# Awesome-Shield-1_0.net
KiCad netlist of a schematic drawn in EAGLE
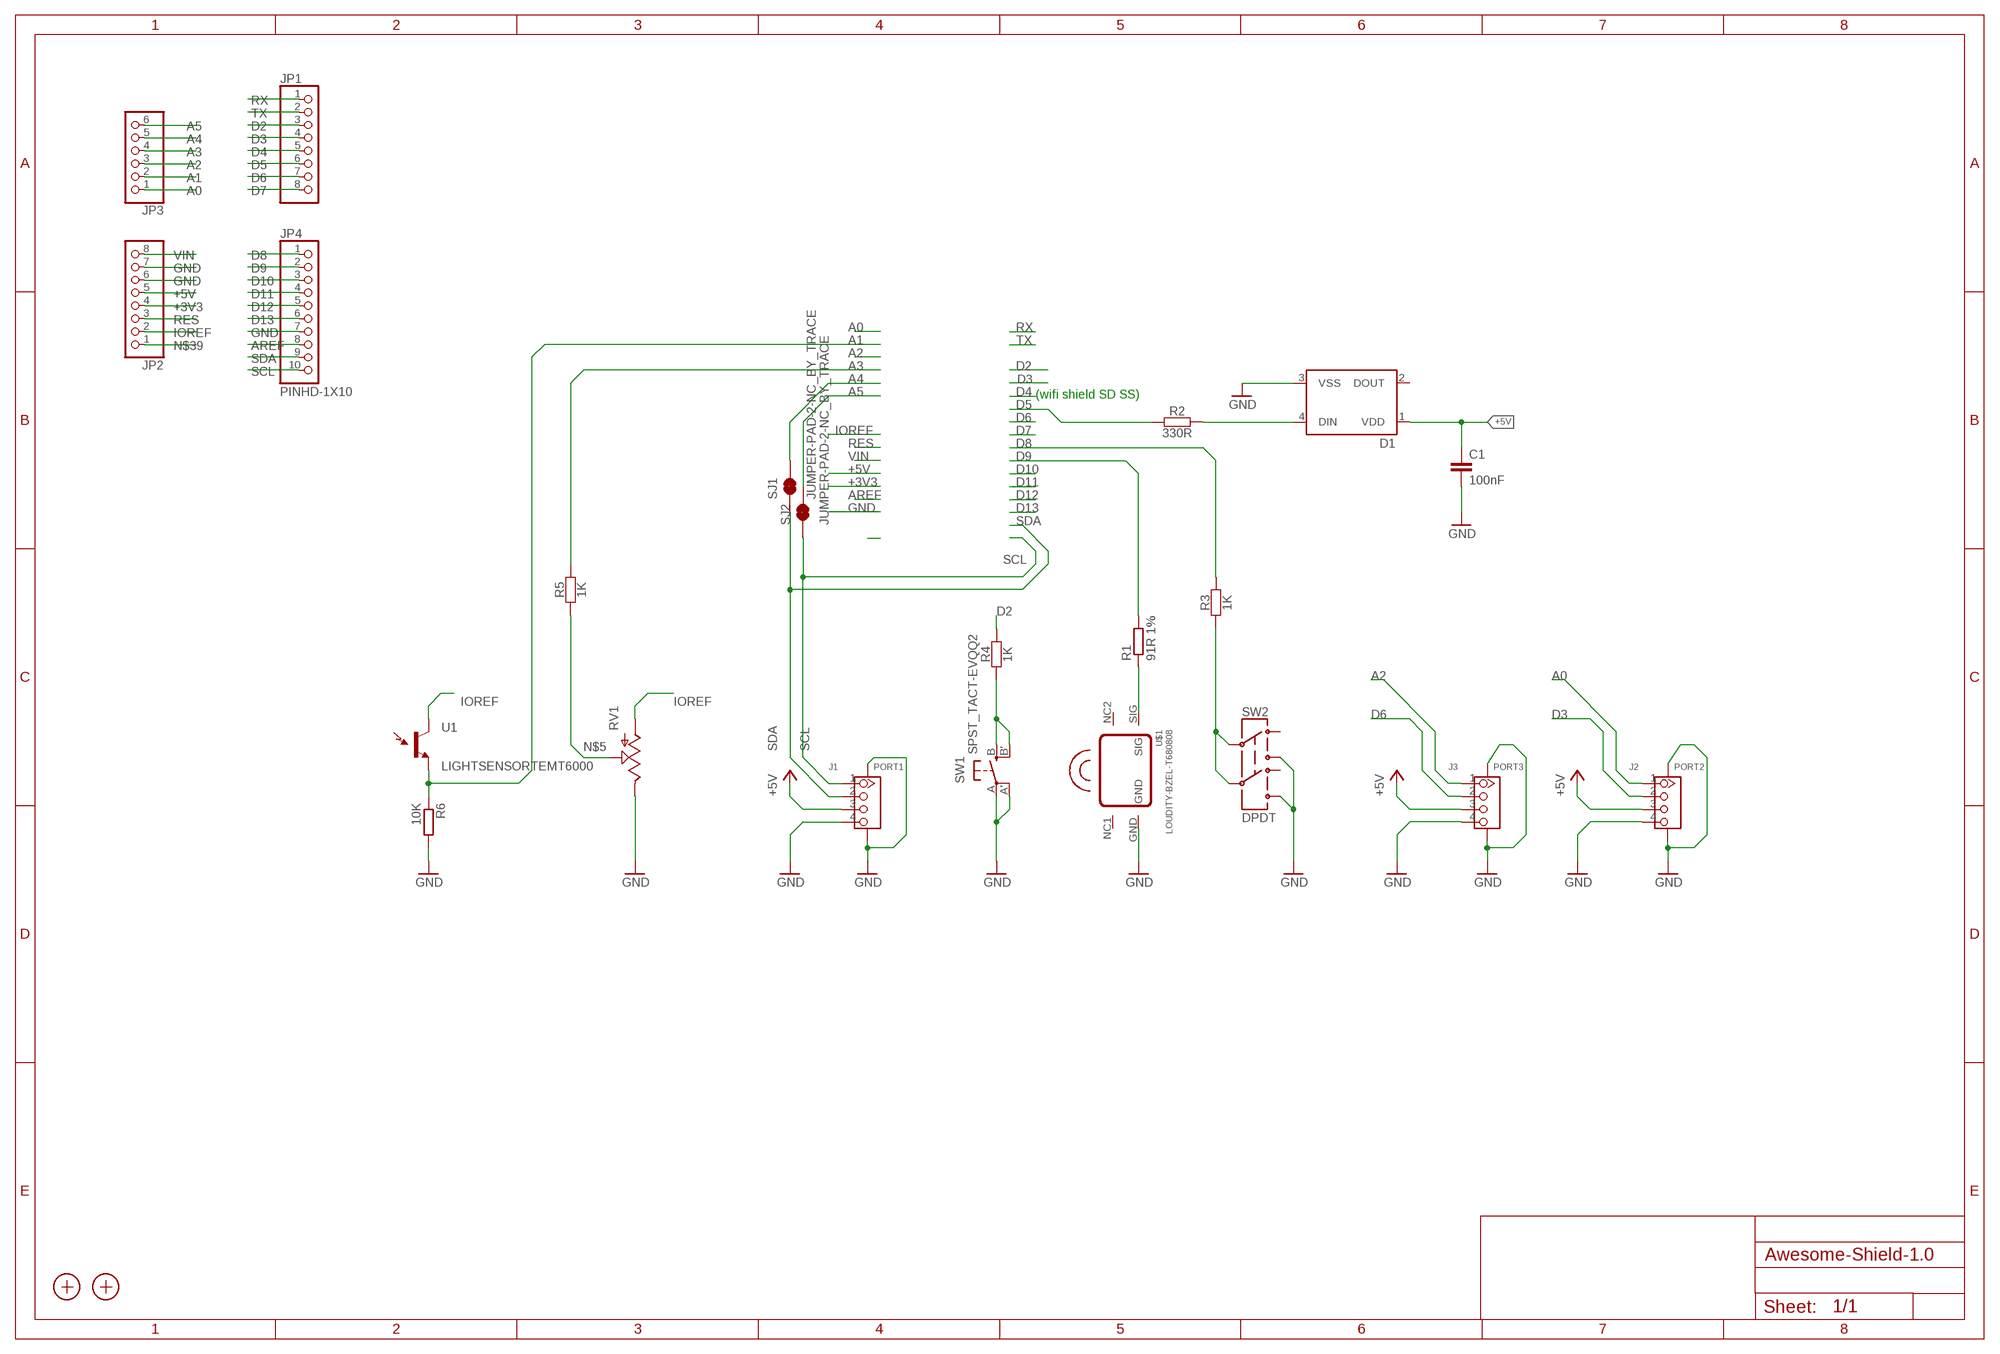
[diagram p0: schematic, sheet 1]

(export (version "E")
  (design (tool "Eeschema 10.0.6"))
  (components
    (comp (ref "C1")
      (value "100nF")
      (footprint "eagle-import:C0603")
      (libsource (lib "eagle-import") (part "C-EUC0603"))
    )
    (comp (ref "D1")
      (value "WS2812B")
      (footprint "eagle-import:WS2812B")
      (libsource (lib "eagle-import") (part "WS2812B"))
    )
    (comp (ref "J1")
      (value "PORT1")
      (footprint "eagle-import:HW4-SMD-2.0")
      (libsource (lib "eagle-import") (part "GROVE-CONNECTOR-SMD(4+2P-2.0)"))
    )
    (comp (ref "J2")
      (value "PORT2")
      (footprint "eagle-import:HW4-SMD-2.0")
      (libsource (lib "eagle-import") (part "GROVE-CONNECTOR-SMD(4+2P-2.0)"))
    )
    (comp (ref "J3")
      (value "PORT3")
      (footprint "eagle-import:HW4-SMD-2.0")
      (libsource (lib "eagle-import") (part "GROVE-CONNECTOR-SMD(4+2P-2.0)"))
    )
    (comp (ref "JP1")
      (value "PINHD-1X8CLEANBIG")
      (footprint "eagle-import:1X08-CLEANBIG")
      (libsource (lib "eagle-import") (part "PINHD-1X8CLEANBIG"))
    )
    (comp (ref "JP2")
      (value "PINHD-1X8CLEANBIG")
      (footprint "eagle-import:1X08-CLEANBIG")
      (libsource (lib "eagle-import") (part "PINHD-1X8CLEANBIG"))
    )
    (comp (ref "JP3")
      (value "PINHD-1X6CLEAN")
      (footprint "eagle-import:1X06-CLEAN")
      (libsource (lib "eagle-import") (part "PINHD-1X6CLEAN"))
    )
    (comp (ref "JP4")
      (value "PINHD-1X10")
      (footprint "eagle-import:1X10-BIG")
      (libsource (lib "eagle-import") (part "PINHD-1X10"))
    )
    (comp (ref "R1")
      (value "91R 1%")
      (footprint "eagle-import:R1206")
      (libsource (lib "eagle-import") (part "R-EU_R1206"))
    )
    (comp (ref "R2")
      (value "330R")
      (footprint "eagle-import:C1206")
      (libsource (lib "eagle-import") (part "RESISTOR-1206"))
    )
    (comp (ref "R3")
      (value "1K")
      (footprint "eagle-import:C0603")
      (libsource (lib "eagle-import") (part "RESISTOR-0603"))
    )
    (comp (ref "R4")
      (value "1K")
      (footprint "eagle-import:C0603")
      (libsource (lib "eagle-import") (part "RESISTOR-0603"))
    )
    (comp (ref "R5")
      (value "1K")
      (footprint "eagle-import:C0603")
      (libsource (lib "eagle-import") (part "RESISTOR-0603"))
    )
    (comp (ref "R6")
      (value "10K")
      (footprint "eagle-import:R1206")
      (libsource (lib "eagle-import") (part "R-EU_R1206"))
    )
    (comp (ref "RV1")
      (value "POT")
      (footprint "eagle-import:ALPS_POT")
      (libsource (lib "eagle-import") (part "POT"))
    )
    (comp (ref "SJ1")
      (value "JUMPER-PAD-2-NC_BY_TRACE")
      (footprint "eagle-import:PAD-JUMPER-2-NC_BY_TRACE_YES_SILK")
      (libsource (lib "eagle-import") (part "JUMPER-PAD-2-NC_BY_TRACE"))
    )
    (comp (ref "SJ2")
      (value "JUMPER-PAD-2-NC_BY_TRACE")
      (footprint "eagle-import:PAD-JUMPER-2-NC_BY_TRACE_YES_SILK")
      (libsource (lib "eagle-import") (part "JUMPER-PAD-2-NC_BY_TRACE"))
    )
    (comp (ref "SW1")
      (value "SPST_TACT-EVQQ2")
      (footprint "eagle-import:EVQ-Q2")
      (libsource (lib "eagle-import") (part "SPST_TACT-EVQQ2"))
    )
    (comp (ref "SW2")
      (value "DPDT")
      (footprint "eagle-import:AYZ0202")
      (libsource (lib "eagle-import") (part "SWITCH-DPDTAYZ0202"))
    )
    (comp (ref "U$1")
      (value "LOUDITY-BZEL-T680808")
      (footprint "eagle-import:SMT-68")
      (libsource (lib "eagle-import") (part "LOUDITY-BZEL-T680808"))
    )
    (comp (ref "U1")
      (value "LIGHTSENSORTEMT6000")
      (footprint "eagle-import:TEMT6000-SEN")
      (libsource (lib "eagle-import") (part "LIGHTSENSORTEMT6000"))
    )
    (comp (ref "X1")
      (value "PASSER-07")
      (footprint "eagle-import:PASSER_07MM")
      (libsource (lib "eagle-import") (part "PASSER-07"))
    )
    (comp (ref "X2")
      (value "PASSER-07")
      (footprint "eagle-import:PASSER_07MM")
      (libsource (lib "eagle-import") (part "PASSER-07"))
    )
  )
  (nets
    (net (code "1") (name "+5V") (class "Default")
      (node (ref "C1") (pin "1") (pinfunction "1_1") (pintype "passive"))
      (node (ref "D1") (pin "1") (pinfunction "VDD_1") (pintype "power_in"))
      (node (ref "J1") (pin "3") (pinfunction "3_3") (pintype "bidirectional"))
      (node (ref "J2") (pin "3") (pinfunction "3_3") (pintype "bidirectional"))
      (node (ref "J3") (pin "3") (pinfunction "3_3") (pintype "bidirectional"))
      (node (ref "JP2") (pin "5") (pinfunction "5_5") (pintype "passive"))
    )
    (net (code "2") (name "/+3V3") (class "Default")
      (node (ref "JP2") (pin "4") (pinfunction "4_4") (pintype "passive"))
    )
    (net (code "3") (name "/A0") (class "Default")
      (node (ref "J2") (pin "1") (pinfunction "1_1") (pintype "bidirectional"))
      (node (ref "JP3") (pin "1") (pinfunction "1_1") (pintype "passive"))
    )
    (net (code "4") (name "/A1") (class "Default")
      (node (ref "JP3") (pin "2") (pinfunction "2_2") (pintype "passive"))
      (node (ref "R6") (pin "1") (pinfunction "1_1") (pintype "passive"))
      (node (ref "U1") (pin "EMITTER") (pinfunction "E1_EMITTER") (pintype "passive"))
    )
    (net (code "5") (name "/A2") (class "Default")
      (node (ref "J3") (pin "1") (pinfunction "1_1") (pintype "bidirectional"))
      (node (ref "JP3") (pin "3") (pinfunction "3_3") (pintype "passive"))
    )
    (net (code "6") (name "/A3") (class "Default")
      (node (ref "JP3") (pin "4") (pinfunction "4_4") (pintype "passive"))
      (node (ref "R5") (pin "2") (pinfunction "2_2") (pintype "passive"))
    )
    (net (code "7") (name "/A4") (class "Default")
      (node (ref "JP3") (pin "5") (pinfunction "5_5") (pintype "passive"))
      (node (ref "SJ1") (pin "2") (pinfunction "2_2") (pintype "passive"))
    )
    (net (code "8") (name "/A5") (class "Default")
      (node (ref "JP3") (pin "6") (pinfunction "6_6") (pintype "passive"))
      (node (ref "SJ2") (pin "2") (pinfunction "2_2") (pintype "passive"))
    )
    (net (code "9") (name "/AREF") (class "Default")
      (node (ref "JP4") (pin "8") (pinfunction "8_8") (pintype "passive"))
    )
    (net (code "10") (name "/D2") (class "Default")
      (node (ref "JP1") (pin "3") (pinfunction "3_3") (pintype "passive"))
      (node (ref "R4") (pin "2") (pinfunction "2_2") (pintype "passive"))
    )
    (net (code "11") (name "/D3") (class "Default")
      (node (ref "J2") (pin "2") (pinfunction "2_2") (pintype "bidirectional"))
      (node (ref "JP1") (pin "4") (pinfunction "4_4") (pintype "passive"))
    )
    (net (code "12") (name "/D4") (class "Default")
      (node (ref "JP1") (pin "5") (pinfunction "5_5") (pintype "passive"))
    )
    (net (code "13") (name "/D5") (class "Default")
      (node (ref "JP1") (pin "6") (pinfunction "6_6") (pintype "passive"))
      (node (ref "R2") (pin "1") (pinfunction "1_1") (pintype "passive"))
    )
    (net (code "14") (name "/D6") (class "Default")
      (node (ref "J3") (pin "2") (pinfunction "2_2") (pintype "bidirectional"))
      (node (ref "JP1") (pin "7") (pinfunction "7_7") (pintype "passive"))
    )
    (net (code "15") (name "/D7") (class "Default")
      (node (ref "JP1") (pin "8") (pinfunction "8_8") (pintype "passive"))
    )
    (net (code "16") (name "/D8") (class "Default")
      (node (ref "JP4") (pin "1") (pinfunction "1_1") (pintype "passive"))
      (node (ref "R3") (pin "2") (pinfunction "2_2") (pintype "passive"))
    )
    (net (code "17") (name "/D9") (class "Default")
      (node (ref "JP4") (pin "2") (pinfunction "2_2") (pintype "passive"))
      (node (ref "R1") (pin "2") (pinfunction "2_2") (pintype "passive"))
    )
    (net (code "18") (name "/D10") (class "Default")
      (node (ref "JP4") (pin "3") (pinfunction "3_3") (pintype "passive"))
    )
    (net (code "19") (name "/D11") (class "Default")
      (node (ref "JP4") (pin "4") (pinfunction "4_4") (pintype "passive"))
    )
    (net (code "20") (name "/D12") (class "Default")
      (node (ref "JP4") (pin "5") (pinfunction "5_5") (pintype "passive"))
    )
    (net (code "21") (name "/D13") (class "Default")
      (node (ref "JP4") (pin "6") (pinfunction "6_6") (pintype "passive"))
    )
    (net (code "22") (name "/IOREF") (class "Default")
      (node (ref "JP2") (pin "2") (pinfunction "2_2") (pintype "passive"))
      (node (ref "RV1") (pin "P$3") (pinfunction "A_P$3") (pintype "passive"))
      (node (ref "U1") (pin "COLLECTOR") (pinfunction "C1_COLLECTOR") (pintype "passive"))
    )
    (net (code "23") (name "/N$5") (class "Default")
      (node (ref "R5") (pin "1") (pinfunction "1_1") (pintype "passive"))
      (node (ref "RV1") (pin "P$2") (pinfunction "S_P$2") (pintype "passive"))
    )
    (net (code "24") (name "/N$39") (class "Default")
      (node (ref "JP2") (pin "1") (pinfunction "1_1") (pintype "passive"))
    )
    (net (code "25") (name "/RES") (class "Default")
      (node (ref "JP2") (pin "3") (pinfunction "3_3") (pintype "passive"))
    )
    (net (code "26") (name "/RX") (class "Default")
      (node (ref "JP1") (pin "1") (pinfunction "1_1") (pintype "passive"))
    )
    (net (code "27") (name "/SCL") (class "Default")
      (node (ref "J1") (pin "1") (pinfunction "1_1") (pintype "bidirectional"))
      (node (ref "JP4") (pin "10") (pinfunction "10_10") (pintype "passive"))
      (node (ref "SJ2") (pin "1") (pinfunction "1_1") (pintype "passive"))
    )
    (net (code "28") (name "/SDA") (class "Default")
      (node (ref "J1") (pin "2") (pinfunction "2_2") (pintype "bidirectional"))
      (node (ref "JP4") (pin "9") (pinfunction "9_9") (pintype "passive"))
      (node (ref "SJ1") (pin "1") (pinfunction "1_1") (pintype "passive"))
    )
    (net (code "29") (name "/TX") (class "Default")
      (node (ref "JP1") (pin "2") (pinfunction "2_2") (pintype "passive"))
    )
    (net (code "30") (name "/VIN") (class "Default")
      (node (ref "JP2") (pin "8") (pinfunction "8_8") (pintype "passive"))
    )
    (net (code "31") (name "GND") (class "Default")
      (node (ref "C1") (pin "2") (pinfunction "2_2") (pintype "passive"))
      (node (ref "D1") (pin "3") (pinfunction "VSS_3") (pintype "power_in"))
      (node (ref "J1") (pin "4") (pinfunction "4_4") (pintype "bidirectional"))
      (node (ref "J1") (pin "SS1") (pinfunction "SS1_SS1") (pintype "bidirectional"))
      (node (ref "J1") (pin "SS2") (pinfunction "SS2_SS2") (pintype "bidirectional"))
      (node (ref "J2") (pin "4") (pinfunction "4_4") (pintype "bidirectional"))
      (node (ref "J2") (pin "SS1") (pinfunction "SS1_SS1") (pintype "bidirectional"))
      (node (ref "J2") (pin "SS2") (pinfunction "SS2_SS2") (pintype "bidirectional"))
      (node (ref "J3") (pin "4") (pinfunction "4_4") (pintype "bidirectional"))
      (node (ref "J3") (pin "SS1") (pinfunction "SS1_SS1") (pintype "bidirectional"))
      (node (ref "J3") (pin "SS2") (pinfunction "SS2_SS2") (pintype "bidirectional"))
      (node (ref "JP2") (pin "6") (pinfunction "6_6") (pintype "passive"))
      (node (ref "JP2") (pin "7") (pinfunction "7_7") (pintype "passive"))
      (node (ref "JP4") (pin "7") (pinfunction "7_7") (pintype "passive"))
      (node (ref "R6") (pin "2") (pinfunction "2_2") (pintype "passive"))
      (node (ref "RV1") (pin "P$1") (pinfunction "E_P$1") (pintype "passive"))
      (node (ref "SW1") (pin "A") (pinfunction "P_A") (pintype "passive"))
      (node (ref "SW1") (pin "A'") (pinfunction "P1_A'") (pintype "passive"))
      (node (ref "SW2") (pin "3") (pinfunction "3_3") (pintype "bidirectional"))
      (node (ref "SW2") (pin "6") (pinfunction "6_6") (pintype "bidirectional"))
      (node (ref "U$1") (pin "GND") (pinfunction "GND_GND") (pintype "bidirectional"))
    )
    (net (code "32") (name "Net-(D1-DIN)") (class "Default")
      (node (ref "D1") (pin "4") (pinfunction "DIN_4") (pintype "input"))
      (node (ref "R2") (pin "2") (pinfunction "2_2") (pintype "passive"))
    )
    (net (code "33") (name "Net-(R1-Pad1)") (class "Default")
      (node (ref "R1") (pin "1") (pinfunction "1_1") (pintype "passive"))
      (node (ref "U$1") (pin "SIG") (pinfunction "SIG_SIG") (pintype "bidirectional"))
    )
    (net (code "34") (name "Net-(R3-Pad1)") (class "Default")
      (node (ref "R3") (pin "1") (pinfunction "1_1") (pintype "passive"))
      (node (ref "SW2") (pin "2") (pinfunction "2_2") (pintype "bidirectional"))
      (node (ref "SW2") (pin "5") (pinfunction "5_5") (pintype "bidirectional"))
    )
    (net (code "35") (name "Net-(SW1-S)") (class "Default")
      (node (ref "R4") (pin "1") (pinfunction "1_1") (pintype "passive"))
      (node (ref "SW1") (pin "B") (pinfunction "S_B") (pintype "passive"))
      (node (ref "SW1") (pin "B'") (pinfunction "S1_B'") (pintype "passive"))
    )
    (net (code "36") (name "unconnected-(D1-DOUT-Pad2)") (class "Default")
      (node (ref "D1") (pin "2") (pinfunction "DOUT_2") (pintype "output"))
    )
    (net (code "37") (name "unconnected-(SW2-Pad1)") (class "Default")
      (node (ref "SW2") (pin "1") (pinfunction "1_1") (pintype "bidirectional"))
    )
    (net (code "38") (name "unconnected-(SW2-Pad4)") (class "Default")
      (node (ref "SW2") (pin "4") (pinfunction "4_4") (pintype "bidirectional"))
    )
    (net (code "39") (name "unconnected-(U$1-NC-PadNC1)") (class "Default")
      (node (ref "U$1") (pin "NC1") (pinfunction "NC_NC1") (pintype "bidirectional"))
    )
    (net (code "40") (name "unconnected-(U$1-NC-PadNC2)") (class "Default")
      (node (ref "U$1") (pin "NC2") (pinfunction "NC_NC2") (pintype "bidirectional"))
    )
  )
)
